# jpwr_v1.net
KiCad netlist of a schematic drawn in EAGLE
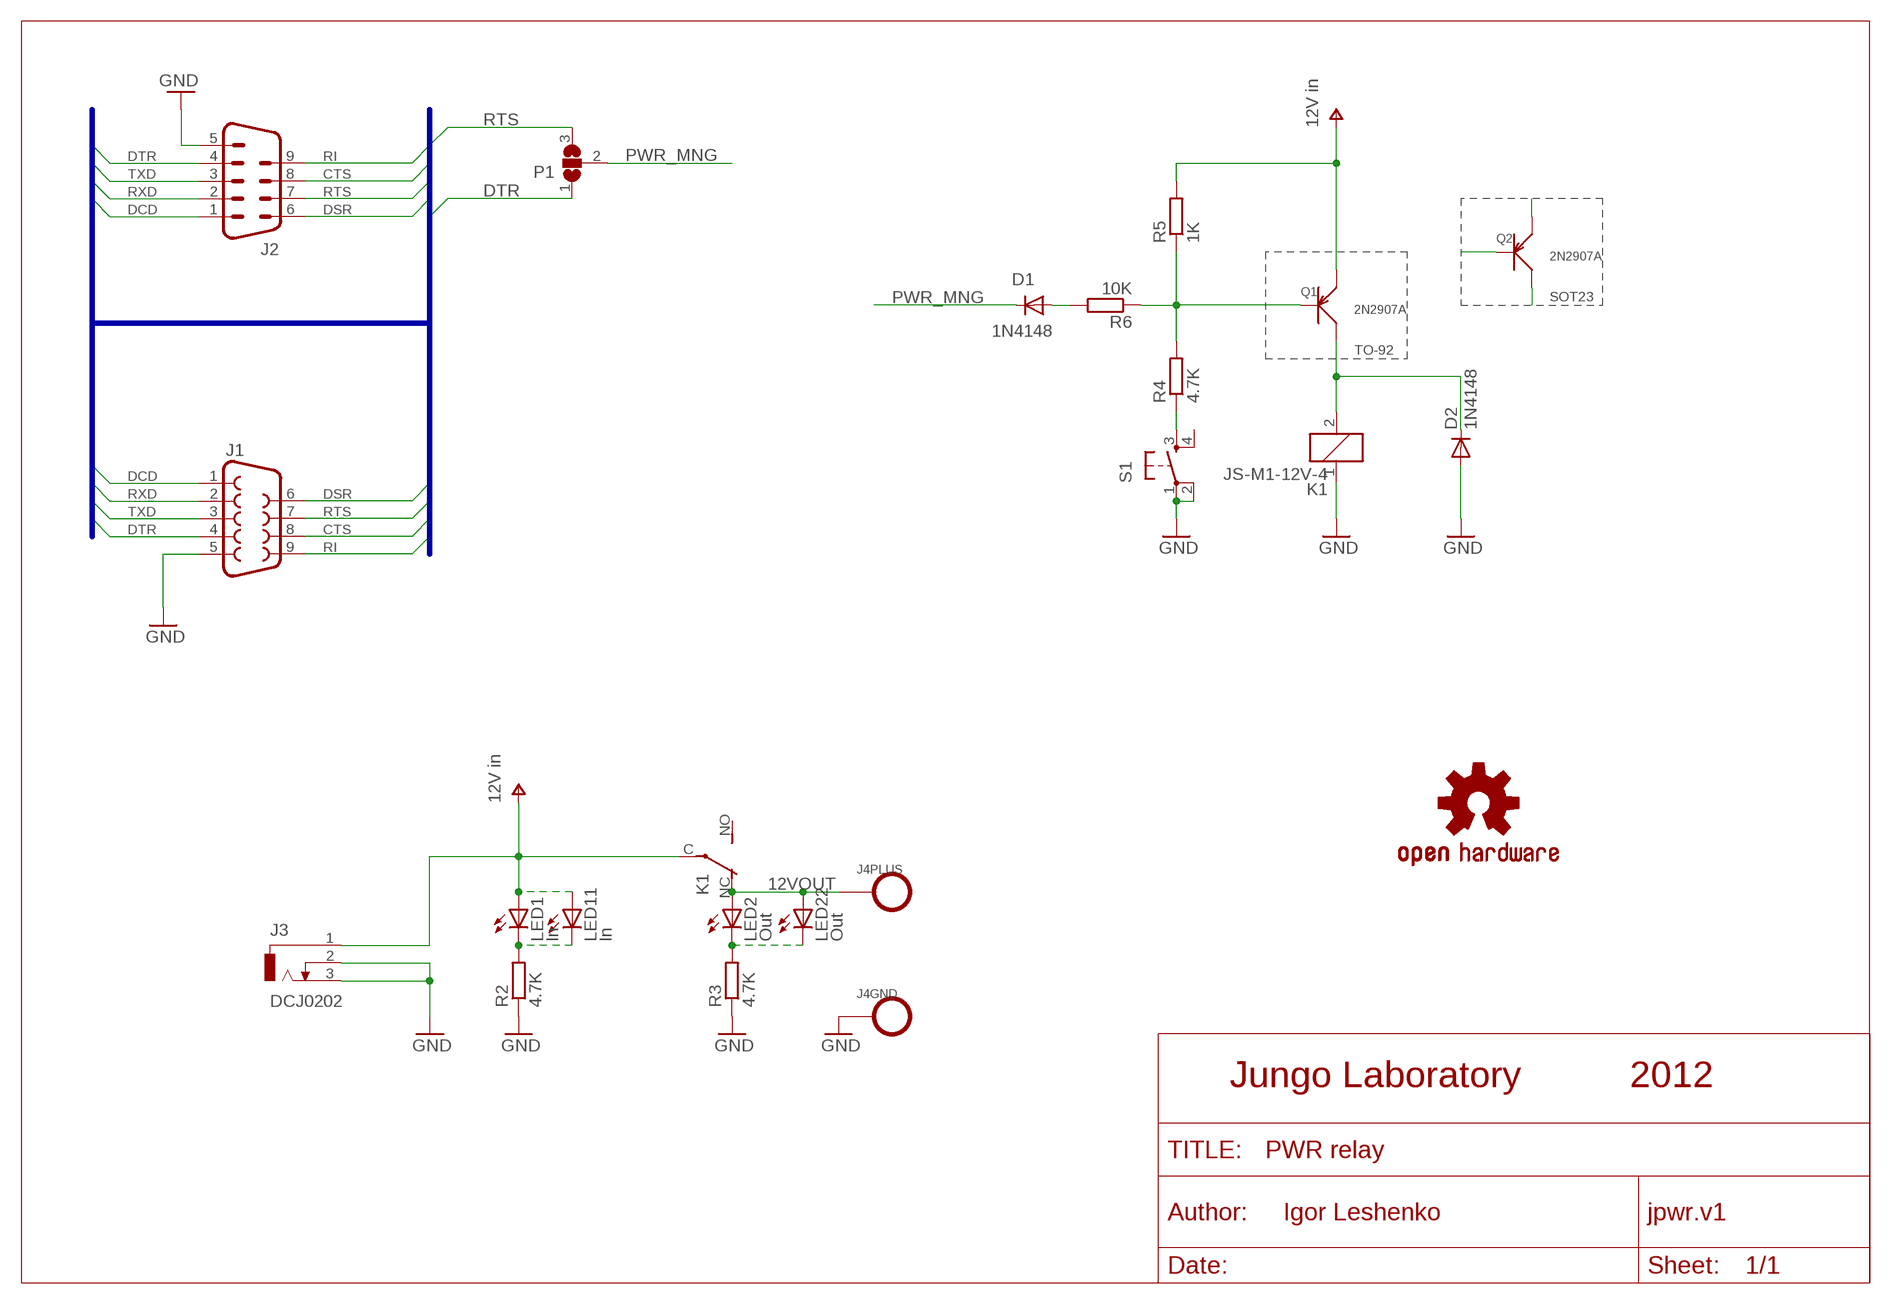
[diagram p0: schematic, sheet 1]

(export (version "E")
  (design (tool "Eeschema 10.0.6"))
  (components
    (comp (ref "D1")
      (value "1N4148")
      (footprint "eagle-import:SOD123")
      (libsource (lib "eagle-import") (part "DIODE-SOD123"))
    )
    (comp (ref "D2")
      (value "1N4148")
      (footprint "eagle-import:SOD123")
      (libsource (lib "eagle-import") (part "DIODE-SOD123"))
    )
    (comp (ref "J1")
      (value "F09D")
      (footprint "eagle-import:F09D")
      (libsource (lib "eagle-import") (part "F09D"))
    )
    (comp (ref "J2")
      (value "M09D")
      (footprint "eagle-import:M09D")
      (libsource (lib "eagle-import") (part "M09D"))
    )
    (comp (ref "J3")
      (value "DCJ0202")
      (footprint "eagle-import:DCJ0202")
      (libsource (lib "eagle-import") (part "DCJ0202"))
    )
    (comp (ref "J4")
      (value "POWER-OUT")
      (footprint "eagle-import:FLEX-POWER")
      (libsource (lib "eagle-import") (part "POWER-OUT"))
    )
    (comp (ref "K1")
      (value "JS-M1-12V-4")
      (footprint "eagle-import:SRD")
      (fields
        (field (name "MPN") "JSM1-12V-4")
        (field (name "MPN_1") "JSM1-12V-4")
        (field (name "OC_FARNELL") "910338")
        (field (name "OC_NEWARK") "13P4552")
      )
      (libsource (lib "eagle-import") (part "JS-M1-12V-4"))
    )
    (comp (ref "LED1")
      (value "In")
      (footprint "eagle-import:CHIPLED_0805")
      (libsource (lib "eagle-import") (part "LEDCHIPLED_0805"))
    )
    (comp (ref "LED2")
      (value "Out")
      (footprint "eagle-import:CHIPLED_0805")
      (libsource (lib "eagle-import") (part "LEDCHIPLED_0805"))
    )
    (comp (ref "LED11")
      (value "In")
      (footprint "eagle-import:CHIPLED_0805")
      (libsource (lib "eagle-import") (part "LEDCHIPLED_0805"))
    )
    (comp (ref "LED22")
      (value "Out")
      (footprint "eagle-import:CHIPLED_0805")
      (libsource (lib "eagle-import") (part "LEDCHIPLED_0805"))
    )
    (comp (ref "P1")
      (value "PAD-SOLDERJUMPER-2WAYT")
      (footprint "eagle-import:3P-SMD-4.8X2")
      (libsource (lib "eagle-import") (part "PAD-SOLDERJUMPER-2WAYT"))
    )
    (comp (ref "Q1")
      (value "2N2907A")
      (footprint "eagle-import:TO-92-TRIANGLE")
      (libsource (lib "eagle-import") (part "TRANSISTOR-PNP-TO-92"))
    )
    (comp (ref "Q2")
      (value "2N2907A")
      (footprint "eagle-import:SOT23")
      (libsource (lib "eagle-import") (part "TRANSISTOR-PNP-SOT23"))
    )
    (comp (ref "R2")
      (value "4.7K")
      (footprint "eagle-import:M0805")
      (libsource (lib "eagle-import") (part "R-EU_M0805"))
    )
    (comp (ref "R3")
      (value "4.7K")
      (footprint "eagle-import:M0805")
      (libsource (lib "eagle-import") (part "R-EU_M0805"))
    )
    (comp (ref "R4")
      (value "4.7K")
      (footprint "eagle-import:M0805")
      (libsource (lib "eagle-import") (part "R-EU_M0805"))
    )
    (comp (ref "R5")
      (value "1K")
      (footprint "eagle-import:M0805")
      (libsource (lib "eagle-import") (part "R-EU_M0805"))
    )
    (comp (ref "R6")
      (value "10K")
      (footprint "eagle-import:M0805")
      (libsource (lib "eagle-import") (part "R-EU_M0805"))
    )
    (comp (ref "S1")
      (value "TAC_SWITCHPTH")
      (footprint "eagle-import:TACTILE-PTH")
      (libsource (lib "eagle-import") (part "TAC_SWITCHPTH"))
    )
    (comp (ref "U$1")
      (value "OSHW-LOGOL")
      (footprint "eagle-import:OSHW-LOGO-L")
      (libsource (lib "eagle-import") (part "OSHW-LOGOL"))
    )
  )
  (nets
    (net (code "1") (name "/12VOUT") (class "Default")
      (node (ref "J4") (pin "1") (pinfunction "P$1_1") (pintype "bidirectional"))
      (node (ref "K1") (pin "NC") (pinfunction "O_NC") (pintype "passive"))
      (node (ref "LED2") (pin "A") (pinfunction "A_A") (pintype "passive"))
      (node (ref "LED22") (pin "A") (pinfunction "A_A") (pintype "passive"))
    )
    (net (code "2") (name "/CTS") (class "Default")
      (node (ref "J1") (pin "8") (pinfunction "8_8") (pintype "passive"))
      (node (ref "J2") (pin "8") (pinfunction "8_8") (pintype "passive"))
    )
    (net (code "3") (name "/DCD") (class "Default")
      (node (ref "J1") (pin "1") (pinfunction "1_1") (pintype "passive"))
      (node (ref "J2") (pin "1") (pinfunction "1_1") (pintype "passive"))
    )
    (net (code "4") (name "/DSR") (class "Default")
      (node (ref "J1") (pin "6") (pinfunction "6_6") (pintype "passive"))
      (node (ref "J2") (pin "6") (pinfunction "6_6") (pintype "passive"))
    )
    (net (code "5") (name "/DTR") (class "Default")
      (node (ref "J1") (pin "4") (pinfunction "4_4") (pintype "passive"))
      (node (ref "J2") (pin "4") (pinfunction "4_4") (pintype "passive"))
      (node (ref "P1") (pin "1") (pinfunction "1_1") (pintype "passive"))
    )
    (net (code "6") (name "/PWR_MNG") (class "Default")
      (node (ref "D1") (pin "C") (pinfunction "C_C") (pintype "passive"))
      (node (ref "P1") (pin "2") (pinfunction "2_2") (pintype "passive"))
    )
    (net (code "7") (name "/Q1_B") (class "Default")
      (node (ref "Q1") (pin "2") (pinfunction "B_2") (pintype "passive"))
      (node (ref "Q2") (pin "1") (pinfunction "B_1") (pintype "passive"))
      (node (ref "R4") (pin "2") (pinfunction "2_2") (pintype "passive"))
      (node (ref "R5") (pin "1") (pinfunction "1_1") (pintype "passive"))
      (node (ref "R6") (pin "1") (pinfunction "1_1") (pintype "passive"))
    )
    (net (code "8") (name "/Q1_C") (class "Default")
      (node (ref "D2") (pin "C") (pinfunction "C_C") (pintype "passive"))
      (node (ref "K1") (pin "2") (pinfunction "2_2") (pintype "passive"))
      (node (ref "Q1") (pin "3") (pinfunction "C_3") (pintype "passive"))
      (node (ref "Q2") (pin "3") (pinfunction "C_3") (pintype "passive"))
    )
    (net (code "9") (name "/RI") (class "Default")
      (node (ref "J1") (pin "9") (pinfunction "9_9") (pintype "passive"))
      (node (ref "J2") (pin "9") (pinfunction "9_9") (pintype "passive"))
    )
    (net (code "10") (name "/RTS") (class "Default")
      (node (ref "J1") (pin "7") (pinfunction "7_7") (pintype "passive"))
      (node (ref "J2") (pin "7") (pinfunction "7_7") (pintype "passive"))
      (node (ref "P1") (pin "3") (pinfunction "3_3") (pintype "passive"))
    )
    (net (code "11") (name "/RXD") (class "Default")
      (node (ref "J1") (pin "2") (pinfunction "2_2") (pintype "passive"))
      (node (ref "J2") (pin "2") (pinfunction "2_2") (pintype "passive"))
    )
    (net (code "12") (name "/TXD") (class "Default")
      (node (ref "J1") (pin "3") (pinfunction "3_3") (pintype "passive"))
      (node (ref "J2") (pin "3") (pinfunction "3_3") (pintype "passive"))
    )
    (net (code "13") (name "12V in") (class "Default")
      (node (ref "J3") (pin "1") (pinfunction "1_1") (pintype "passive"))
      (node (ref "K1") (pin "C") (pinfunction "P_C") (pintype "passive"))
      (node (ref "LED1") (pin "A") (pinfunction "A_A") (pintype "passive"))
      (node (ref "LED11") (pin "A") (pinfunction "A_A") (pintype "passive"))
      (node (ref "Q1") (pin "1") (pinfunction "E_1") (pintype "passive"))
      (node (ref "Q2") (pin "2") (pinfunction "E_2") (pintype "passive"))
      (node (ref "R5") (pin "2") (pinfunction "2_2") (pintype "passive"))
    )
    (net (code "14") (name "GND") (class "Default")
      (node (ref "D2") (pin "A") (pinfunction "A_A") (pintype "passive"))
      (node (ref "J1") (pin "5") (pinfunction "5_5") (pintype "passive"))
      (node (ref "J2") (pin "5") (pinfunction "5_5") (pintype "passive"))
      (node (ref "J3") (pin "2") (pinfunction "2_2") (pintype "passive"))
      (node (ref "J3") (pin "3") (pinfunction "3_3") (pintype "passive"))
      (node (ref "J4") (pin "2") (pinfunction "P$1_2") (pintype "bidirectional"))
      (node (ref "K1") (pin "1") (pinfunction "1_1") (pintype "passive"))
      (node (ref "R2") (pin "1") (pinfunction "1_1") (pintype "passive"))
      (node (ref "R3") (pin "1") (pinfunction "1_1") (pintype "passive"))
      (node (ref "S1") (pin "1") (pinfunction "1_1") (pintype "passive"))
      (node (ref "S1") (pin "2") (pinfunction "2_2") (pintype "passive"))
    )
    (net (code "15") (name "Net-(D1-PadA)") (class "Default")
      (node (ref "D1") (pin "A") (pinfunction "A_A") (pintype "passive"))
      (node (ref "R6") (pin "2") (pinfunction "2_2") (pintype "passive"))
    )
    (net (code "16") (name "Net-(LED1-PadC)") (class "Default")
      (node (ref "LED1") (pin "C") (pinfunction "C_C") (pintype "passive"))
      (node (ref "LED11") (pin "C") (pinfunction "C_C") (pintype "passive"))
      (node (ref "R2") (pin "2") (pinfunction "2_2") (pintype "passive"))
    )
    (net (code "17") (name "Net-(LED2-PadC)") (class "Default")
      (node (ref "LED2") (pin "C") (pinfunction "C_C") (pintype "passive"))
      (node (ref "LED22") (pin "C") (pinfunction "C_C") (pintype "passive"))
      (node (ref "R3") (pin "2") (pinfunction "2_2") (pintype "passive"))
    )
    (net (code "18") (name "Net-(R4-Pad1)") (class "Default")
      (node (ref "R4") (pin "1") (pinfunction "1_1") (pintype "passive"))
      (node (ref "S1") (pin "3") (pinfunction "3_3") (pintype "passive"))
    )
    (net (code "19") (name "unconnected-(K1B-S-PadNO)") (class "Default")
      (node (ref "K1") (pin "NO") (pinfunction "S_NO") (pintype "passive"))
    )
    (net (code "20") (name "unconnected-(S1-Pad4)") (class "Default")
      (node (ref "S1") (pin "4") (pinfunction "4_4") (pintype "passive"))
    )
  )
)
